# ZED-F9T.net
KiCad netlist of a schematic drawn in Altium Designer
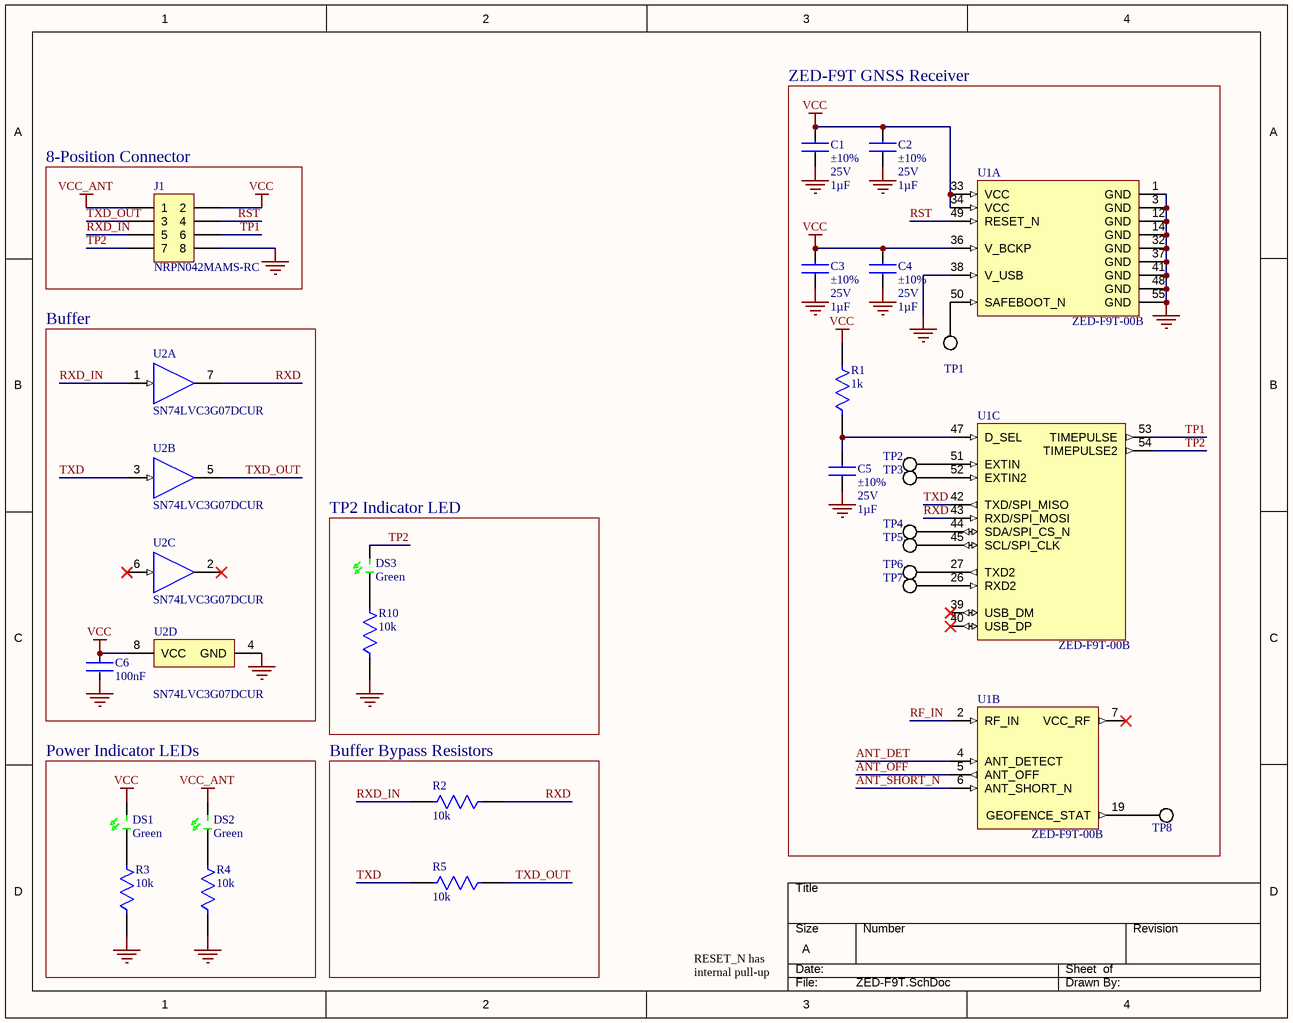
[diagram p0: ZED-F9T.SchDoc]

(export (version "E")
  (design (tool "Eeschema 10.0.6"))
  (components
    (comp (ref "C1")
      (value "Murata_GRM155R61E105KA12D")
      (footprint "CAPC1005X055N")
      (description "CAP, CER, X5R, 1UF, 10%, 25V, 0402, 0.55MM T")
      (fields
        (field (name "MANUFACTURER PART NUMBER") "GRM155R61E105KA12D")
        (field (name "TOLERANCE") "±10%")
        (field (name "VOLTAGE RATING") "25V")
        (field (name "MANUFACTURER") "Murata")
        (field (name "CAPACITANCE") "1µF")
      )
      (libsource (lib "RL Research Altium Server") (part "Capacitor_300mil"))
    )
    (comp (ref "C2")
      (value "Murata_GRM155R61E105KA12D")
      (footprint "CAPC1005X055N")
      (description "CAP, CER, X5R, 1UF, 10%, 25V, 0402, 0.55MM T")
      (fields
        (field (name "MANUFACTURER PART NUMBER") "GRM155R61E105KA12D")
        (field (name "TOLERANCE") "±10%")
        (field (name "VOLTAGE RATING") "25V")
        (field (name "MANUFACTURER") "Murata")
        (field (name "CAPACITANCE") "1µF")
      )
      (libsource (lib "RL Research Altium Server") (part "Capacitor_300mil"))
    )
    (comp (ref "C3")
      (value "Murata_GRM155R61E105KA12D")
      (footprint "CAPC1005X055N")
      (description "CAP, CER, X5R, 1UF, 10%, 25V, 0402, 0.55MM T")
      (fields
        (field (name "MANUFACTURER PART NUMBER") "GRM155R61E105KA12D")
        (field (name "TOLERANCE") "±10%")
        (field (name "VOLTAGE RATING") "25V")
        (field (name "MANUFACTURER") "Murata")
        (field (name "CAPACITANCE") "1µF")
      )
      (libsource (lib "RL Research Altium Server") (part "Capacitor_300mil"))
    )
    (comp (ref "C4")
      (value "Murata_GRM155R61E105KA12D")
      (footprint "CAPC1005X055N")
      (description "CAP, CER, X5R, 1UF, 10%, 25V, 0402, 0.55MM T")
      (fields
        (field (name "MANUFACTURER PART NUMBER") "GRM155R61E105KA12D")
        (field (name "TOLERANCE") "±10%")
        (field (name "VOLTAGE RATING") "25V")
        (field (name "MANUFACTURER") "Murata")
        (field (name "CAPACITANCE") "1µF")
      )
      (libsource (lib "RL Research Altium Server") (part "Capacitor_300mil"))
    )
    (comp (ref "C5")
      (value "Murata_GRM155R61E105KA12D")
      (footprint "CAPC1005X055N")
      (description "CAP, CER, X5R, 1UF, 10%, 25V, 0402, 0.55MM T")
      (fields
        (field (name "MANUFACTURER PART NUMBER") "GRM155R61E105KA12D")
        (field (name "TOLERANCE") "±10%")
        (field (name "VOLTAGE RATING") "25V")
        (field (name "MANUFACTURER") "Murata")
        (field (name "CAPACITANCE") "1µF")
      )
      (libsource (lib "RL Research Altium Server") (part "Capacitor_300mil"))
    )
    (comp (ref "C6")
      (value "100nF")
      (footprint "FP-0402-L_1_0_0_05-W_0_5-IPC_B")
      (description "None")
      (fields (field (name "TOLERANCE") "10%"))
      (libsource (lib "Altium Content Vault") (part "b4654b650e69147ec39a6b967a45e02"))
    )
    (comp (ref "DS1")
      (value "Lumex_SML-LXFM0603SUGCTR")
      (footprint "LEDS160X80X110-2N_LXFM0603-GR")
      (description "LED, GREEN, 574NM, 20MA, 20MCD MIN, 2.5VF MAX, 0603, 1.10MM T")
      (fields
        (field (name "INTERNAL PART NUMBER") "838-00422-00")
        (field (name "MANUFACTURER") "Lumex Opto/Components Inc.")
        (field (name "COLOR") "Green")
      )
      (libsource (lib "RL Research Altium Server") (part "LED_Green_300mil"))
    )
    (comp (ref "DS2")
      (value "Lumex_SML-LXFM0603SUGCTR")
      (footprint "LEDS160X80X110-2N_LXFM0603-GR")
      (description "LED, GREEN, 574NM, 20MA, 20MCD MIN, 2.5VF MAX, 0603, 1.10MM T")
      (fields
        (field (name "INTERNAL PART NUMBER") "838-00422-00")
        (field (name "MANUFACTURER") "Lumex Opto/Components Inc.")
        (field (name "COLOR") "Green")
      )
      (libsource (lib "RL Research Altium Server") (part "LED_Green_300mil"))
    )
    (comp (ref "DS3")
      (value "Lumex_SML-LXFM0603SUGCTR")
      (footprint "LEDS160X80X110-2N_LXFM0603-GR")
      (description "LED, GREEN, 574NM, 20MA, 20MCD MIN, 2.5VF MAX, 0603, 1.10MM T")
      (fields
        (field (name "INTERNAL PART NUMBER") "838-00422-00")
        (field (name "MANUFACTURER") "Lumex Opto/Components Inc.")
        (field (name "COLOR") "Green")
      )
      (libsource (lib "RL Research Altium Server") (part "LED_Green_300mil"))
    )
    (comp (ref "J1")
      (value "NRPN042MAMS-RC")
      (footprint "NRPN042MAMS-RC")
      (description "Dual Row 8 Position 2 mm Pitch Surface Mount Header")
      (fields (field (name "MANUFACTURER") "Sullins"))
      (libsource (lib "GNSS_Receiver_Library") (part "NRPN042MAMS-RC"))
    )
    (comp (ref "R1")
      (value "1k")
      (footprint "FP-RMCF0402-MFG")
      (description "1kΩ ±1% 0.063W 0402 Thick Film Chip Resistor AEC-Q200 compliant")
      (fields (field (name "TOLERANCE") "1%"))
      (libsource (lib "Altium Content Vault") (part "1029c3af85768c4190bb7ad29bc67b5"))
    )
    (comp (ref "R2")
      (value "10k")
      (footprint "FP-RMCF0402-IPC_C")
      (description "10kΩ ±1% 0.063W 0402 Thick Film Chip Resistor AEC-Q200 compliant")
      (fields (field (name "TOLERANCE") "1%"))
      (libsource (lib "Altium Content Vault") (part "1029c3af85768c4190bb7ad29bc67b5"))
    )
    (comp (ref "R3")
      (value "10k")
      (footprint "FP-RMCF0402-IPC_C")
      (description "10kΩ ±1% 0.063W 0402 Thick Film Chip Resistor AEC-Q200 compliant")
      (fields (field (name "TOLERANCE") "1%"))
      (libsource (lib "Altium Content Vault") (part "1029c3af85768c4190bb7ad29bc67b5"))
    )
    (comp (ref "R4")
      (value "10k")
      (footprint "FP-RMCF0402-IPC_C")
      (description "10kΩ ±1% 0.063W 0402 Thick Film Chip Resistor AEC-Q200 compliant")
      (fields (field (name "TOLERANCE") "1%"))
      (libsource (lib "Altium Content Vault") (part "1029c3af85768c4190bb7ad29bc67b5"))
    )
    (comp (ref "R5")
      (value "10k")
      (footprint "FP-RMCF0402-IPC_C")
      (description "10kΩ ±1% 0.063W 0402 Thick Film Chip Resistor AEC-Q200 compliant")
      (fields (field (name "TOLERANCE") "1%"))
      (libsource (lib "Altium Content Vault") (part "1029c3af85768c4190bb7ad29bc67b5"))
    )
    (comp (ref "R10")
      (value "10k")
      (footprint "FP-RMCF0402-IPC_C")
      (description "10kΩ ±1% 0.063W 0402 Thick Film Chip Resistor AEC-Q200 compliant")
      (fields (field (name "TOLERANCE") "1%"))
      (libsource (lib "Altium Content Vault") (part "1029c3af85768c4190bb7ad29bc67b5"))
    )
    (comp (ref "TP1")
      (value "SMT_100DIA")
      (footprint "TP001V_SMT_100DIA")
      (description "TEST POINT, PC, SMT, 1.00MM DIA")
      (libsource (lib "RL Research Altium Server") (part "TP_NoColor_001pin_No_BOM"))
    )
    (comp (ref "TP2")
      (value "SMT_100DIA")
      (footprint "TP001V_SMT_100DIA")
      (description "TEST POINT, PC, SMT, 1.00MM DIA")
      (libsource (lib "RL Research Altium Server") (part "TP_NoColor_001pin_No_BOM"))
    )
    (comp (ref "TP3")
      (value "SMT_100DIA")
      (footprint "TP001V_SMT_100DIA")
      (description "TEST POINT, PC, SMT, 1.00MM DIA")
      (libsource (lib "RL Research Altium Server") (part "TP_NoColor_001pin_No_BOM"))
    )
    (comp (ref "TP4")
      (value "SMT_100DIA")
      (footprint "TP001V_SMT_100DIA")
      (description "TEST POINT, PC, SMT, 1.00MM DIA")
      (libsource (lib "RL Research Altium Server") (part "TP_NoColor_001pin_No_BOM"))
    )
    (comp (ref "TP5")
      (value "SMT_100DIA")
      (footprint "TP001V_SMT_100DIA")
      (description "TEST POINT, PC, SMT, 1.00MM DIA")
      (libsource (lib "RL Research Altium Server") (part "TP_NoColor_001pin_No_BOM"))
    )
    (comp (ref "TP6")
      (value "SMT_100DIA")
      (footprint "TP001V_SMT_100DIA")
      (description "TEST POINT, PC, SMT, 1.00MM DIA")
      (libsource (lib "RL Research Altium Server") (part "TP_NoColor_001pin_No_BOM"))
    )
    (comp (ref "TP7")
      (value "SMT_100DIA")
      (footprint "TP001V_SMT_100DIA")
      (description "TEST POINT, PC, SMT, 1.00MM DIA")
      (libsource (lib "RL Research Altium Server") (part "TP_NoColor_001pin_No_BOM"))
    )
    (comp (ref "TP8")
      (value "SMT_100DIA")
      (footprint "TP001V_SMT_100DIA")
      (description "TEST POINT, PC, SMT, 1.00MM DIA")
      (libsource (lib "RL Research Altium Server") (part "TP_NoColor_001pin_No_BOM"))
    )
    (comp (ref "U1")
      (value "ZED-F9T-00B")
      (footprint "GPS_ZED-F9T")
      (description "Multi-band GNSS Receiver with Nanosecond-level Timing Accuracy")
      (fields (field (name "MANUFACTURER") "u-blox"))
      (libsource (lib "GNSS_Receiver_Library") (part "GPS_ZED-F9T"))
    )
    (comp (ref "U2")
      (value "SN74LVC3G07DCUR")
      (footprint "DCU0008A_N")
      (description "Triple Buffer/Driver With Open-Drain Output, DCU0008A, LARGE T&R")
      (fields
        (field (name "GENERIC PART NUMBER") "SN74LVC3G07")
        (field (name "MANUFACTURER") "Texas Instruments")
      )
      (libsource (lib "Altium Content Vault") (part "TI-SN74XXX3G0X-XX-8"))
    )
  )
  (nets
    (net (code "1") (name "/ANT_DET") (class "Default")
      (node (ref "U1") (pin "4") (pinfunction "ANT_DETECT_4") (pintype "input"))
    )
    (net (code "2") (name "/ANT_OFF") (class "Default")
      (node (ref "U1") (pin "5") (pinfunction "ANT_OFF_5") (pintype "output"))
    )
    (net (code "3") (name "/ANT_SHORT_N") (class "Default")
      (node (ref "U1") (pin "6") (pinfunction "ANT_SHORT_N_6") (pintype "input"))
    )
    (net (code "4") (name "/RF_IN") (class "Default")
      (node (ref "U1") (pin "2") (pinfunction "RF_IN_2") (pintype "input"))
    )
    (net (code "5") (name "/RST") (class "Default")
      (node (ref "J1") (pin "4") (pinfunction "4_4") (pintype "passive"))
      (node (ref "U1") (pin "49") (pinfunction "RESET_N_49") (pintype "input"))
    )
    (net (code "6") (name "/RXD") (class "Default")
      (node (ref "R2") (pin "1") (pinfunction "1_1") (pintype "passive"))
      (node (ref "U1") (pin "43") (pinfunction "RXD/SPI_MOSI_43") (pintype "input"))
      (node (ref "U2") (pin "7") (pinfunction "1Y_7") (pintype "open_collector"))
    )
    (net (code "7") (name "/RXD_IN") (class "Default")
      (node (ref "J1") (pin "5") (pinfunction "5_5") (pintype "passive"))
      (node (ref "R2") (pin "2") (pinfunction "2_2") (pintype "passive"))
      (node (ref "U2") (pin "1") (pinfunction "1A_1") (pintype "input"))
    )
    (net (code "8") (name "/TP1") (class "Default")
      (node (ref "J1") (pin "6") (pinfunction "6_6") (pintype "passive"))
      (node (ref "U1") (pin "53") (pinfunction "TIMEPULSE_53") (pintype "output"))
    )
    (net (code "9") (name "/TP2") (class "Default")
      (node (ref "DS3") (pin "A") (pinfunction "Anode_A") (pintype "passive"))
      (node (ref "J1") (pin "7") (pinfunction "7_7") (pintype "passive"))
      (node (ref "U1") (pin "54") (pinfunction "TIMEPULSE2_54") (pintype "output"))
    )
    (net (code "10") (name "/TXD") (class "Default")
      (node (ref "R5") (pin "2") (pinfunction "2_2") (pintype "passive"))
      (node (ref "U1") (pin "42") (pinfunction "TXD/SPI_MISO_42") (pintype "output"))
      (node (ref "U2") (pin "3") (pinfunction "2A_3") (pintype "input"))
    )
    (net (code "11") (name "/TXD_OUT") (class "Default")
      (node (ref "J1") (pin "3") (pinfunction "3_3") (pintype "passive"))
      (node (ref "R5") (pin "1") (pinfunction "1_1") (pintype "passive"))
      (node (ref "U2") (pin "5") (pinfunction "2Y_5") (pintype "open_collector"))
    )
    (net (code "12") (name "GND") (class "Default")
      (node (ref "C1") (pin "2") (pinfunction "2_2") (pintype "passive"))
      (node (ref "C2") (pin "2") (pinfunction "2_2") (pintype "passive"))
      (node (ref "C3") (pin "2") (pinfunction "2_2") (pintype "passive"))
      (node (ref "C4") (pin "2") (pinfunction "2_2") (pintype "passive"))
      (node (ref "C5") (pin "2") (pinfunction "2_2") (pintype "passive"))
      (node (ref "C6") (pin "2") (pinfunction "2_2") (pintype "passive"))
      (node (ref "J1") (pin "8") (pinfunction "8_8") (pintype "passive"))
      (node (ref "R10") (pin "1") (pinfunction "1_1") (pintype "passive"))
      (node (ref "R3") (pin "1") (pinfunction "1_1") (pintype "passive"))
      (node (ref "R4") (pin "1") (pinfunction "1_1") (pintype "passive"))
      (node (ref "U1") (pin "1") (pinfunction "GND_1") (pintype "passive"))
      (node (ref "U1") (pin "12") (pinfunction "GND_12") (pintype "passive"))
      (node (ref "U1") (pin "14") (pinfunction "GND_14") (pintype "passive"))
      (node (ref "U1") (pin "3") (pinfunction "GND_3") (pintype "passive"))
      (node (ref "U1") (pin "32") (pinfunction "GND_32") (pintype "passive"))
      (node (ref "U1") (pin "37") (pinfunction "GND_37") (pintype "passive"))
      (node (ref "U1") (pin "38") (pinfunction "V_USB_38") (pintype "input"))
      (node (ref "U1") (pin "41") (pinfunction "GND_41") (pintype "passive"))
      (node (ref "U1") (pin "48") (pinfunction "GND_48") (pintype "passive"))
      (node (ref "U1") (pin "55") (pinfunction "GND_55") (pintype "passive"))
      (node (ref "U2") (pin "4") (pinfunction "GND_4") (pintype "power_in"))
    )
    (net (code "13") (name "Net-(DS1-Cathode)") (class "Default")
      (node (ref "DS1") (pin "K") (pinfunction "Cathode_K") (pintype "passive"))
      (node (ref "R3") (pin "2") (pinfunction "2_2") (pintype "passive"))
    )
    (net (code "14") (name "Net-(DS2-Cathode)") (class "Default")
      (node (ref "DS2") (pin "K") (pinfunction "Cathode_K") (pintype "passive"))
      (node (ref "R4") (pin "2") (pinfunction "2_2") (pintype "passive"))
    )
    (net (code "15") (name "Net-(DS3-Cathode)") (class "Default")
      (node (ref "DS3") (pin "K") (pinfunction "Cathode_K") (pintype "passive"))
      (node (ref "R10") (pin "2") (pinfunction "2_2") (pintype "passive"))
    )
    (net (code "16") (name "Net-(U1A-SAFEBOOT_N)") (class "Default")
      (node (ref "TP1") (pin "1") (pinfunction "1_1") (pintype "passive"))
      (node (ref "U1") (pin "50") (pinfunction "SAFEBOOT_N_50") (pintype "input"))
    )
    (net (code "17") (name "Net-(U1B-GEOFENCE_STAT)") (class "Default")
      (node (ref "TP8") (pin "1") (pinfunction "1_1") (pintype "passive"))
      (node (ref "U1") (pin "19") (pinfunction "GEOFENCE_STAT_19") (pintype "output"))
    )
    (net (code "18") (name "Net-(U1C-D_SEL)") (class "Default")
      (node (ref "C5") (pin "1") (pinfunction "1_1") (pintype "passive"))
      (node (ref "R1") (pin "1") (pinfunction "1_1") (pintype "passive"))
      (node (ref "U1") (pin "47") (pinfunction "D_SEL_47") (pintype "input"))
    )
    (net (code "19") (name "Net-(U1C-EXTIN)") (class "Default")
      (node (ref "TP2") (pin "1") (pinfunction "1_1") (pintype "passive"))
      (node (ref "U1") (pin "51") (pinfunction "EXTIN_51") (pintype "input"))
    )
    (net (code "20") (name "Net-(U1C-EXTIN2)") (class "Default")
      (node (ref "TP3") (pin "1") (pinfunction "1_1") (pintype "passive"))
      (node (ref "U1") (pin "52") (pinfunction "EXTIN2_52") (pintype "input"))
    )
    (net (code "21") (name "Net-(U1C-RXD2)") (class "Default")
      (node (ref "TP7") (pin "1") (pinfunction "1_1") (pintype "passive"))
      (node (ref "U1") (pin "26") (pinfunction "RXD2_26") (pintype "input"))
    )
    (net (code "22") (name "Net-(U1C-SCL{slash}SPI_CLK)") (class "Default")
      (node (ref "TP5") (pin "1") (pinfunction "1_1") (pintype "passive"))
      (node (ref "U1") (pin "45") (pinfunction "SCL/SPI_CLK_45") (pintype "bidirectional"))
    )
    (net (code "23") (name "Net-(U1C-SDA{slash}SPI_CS_N)") (class "Default")
      (node (ref "TP4") (pin "1") (pinfunction "1_1") (pintype "passive"))
      (node (ref "U1") (pin "44") (pinfunction "SDA/SPI_CS_N_44") (pintype "bidirectional"))
    )
    (net (code "24") (name "Net-(U1C-TXD2)") (class "Default")
      (node (ref "TP6") (pin "1") (pinfunction "1_1") (pintype "passive"))
      (node (ref "U1") (pin "27") (pinfunction "TXD2_27") (pintype "output"))
    )
    (net (code "25") (name "VCC") (class "Default")
      (node (ref "C1") (pin "1") (pinfunction "1_1") (pintype "passive"))
      (node (ref "C2") (pin "1") (pinfunction "1_1") (pintype "passive"))
      (node (ref "C3") (pin "1") (pinfunction "1_1") (pintype "passive"))
      (node (ref "C4") (pin "1") (pinfunction "1_1") (pintype "passive"))
      (node (ref "C6") (pin "1") (pinfunction "1_1") (pintype "passive"))
      (node (ref "DS1") (pin "A") (pinfunction "Anode_A") (pintype "passive"))
      (node (ref "J1") (pin "2") (pinfunction "2_2") (pintype "passive"))
      (node (ref "R1") (pin "2") (pinfunction "2_2") (pintype "passive"))
      (node (ref "U1") (pin "33") (pinfunction "VCC_33") (pintype "input"))
      (node (ref "U1") (pin "34") (pinfunction "VCC_34") (pintype "input"))
      (node (ref "U1") (pin "36") (pinfunction "V_BCKP_36") (pintype "input"))
      (node (ref "U2") (pin "8") (pinfunction "VCC_8") (pintype "power_in"))
    )
    (net (code "26") (name "VCC_ANT") (class "Default")
      (node (ref "DS2") (pin "A") (pinfunction "Anode_A") (pintype "passive"))
      (node (ref "J1") (pin "1") (pinfunction "1_1") (pintype "passive"))
    )
    (net (code "27") (name "unconnected-(U1B-VCC_RF-Pad7)") (class "Default")
      (node (ref "U1") (pin "7") (pinfunction "VCC_RF_7") (pintype "output+no_connect"))
    )
    (net (code "28") (name "unconnected-(U1C-USB_DM-Pad39)") (class "Default")
      (node (ref "U1") (pin "39") (pinfunction "USB_DM_39") (pintype "bidirectional+no_connect"))
    )
    (net (code "29") (name "unconnected-(U1C-USB_DP-Pad40)") (class "Default")
      (node (ref "U1") (pin "40") (pinfunction "USB_DP_40") (pintype "bidirectional+no_connect"))
    )
    (net (code "30") (name "unconnected-(U2C-3A-Pad6)") (class "Default")
      (node (ref "U2") (pin "6") (pinfunction "3A_6") (pintype "input+no_connect"))
    )
    (net (code "31") (name "unconnected-(U2C-3Y-Pad2)") (class "Default")
      (node (ref "U2") (pin "2") (pinfunction "3Y_2") (pintype "open_collector+no_connect"))
    )
  )
)
